# RF_Xbee.net
KiCad netlist of a schematic drawn in Altium Designer
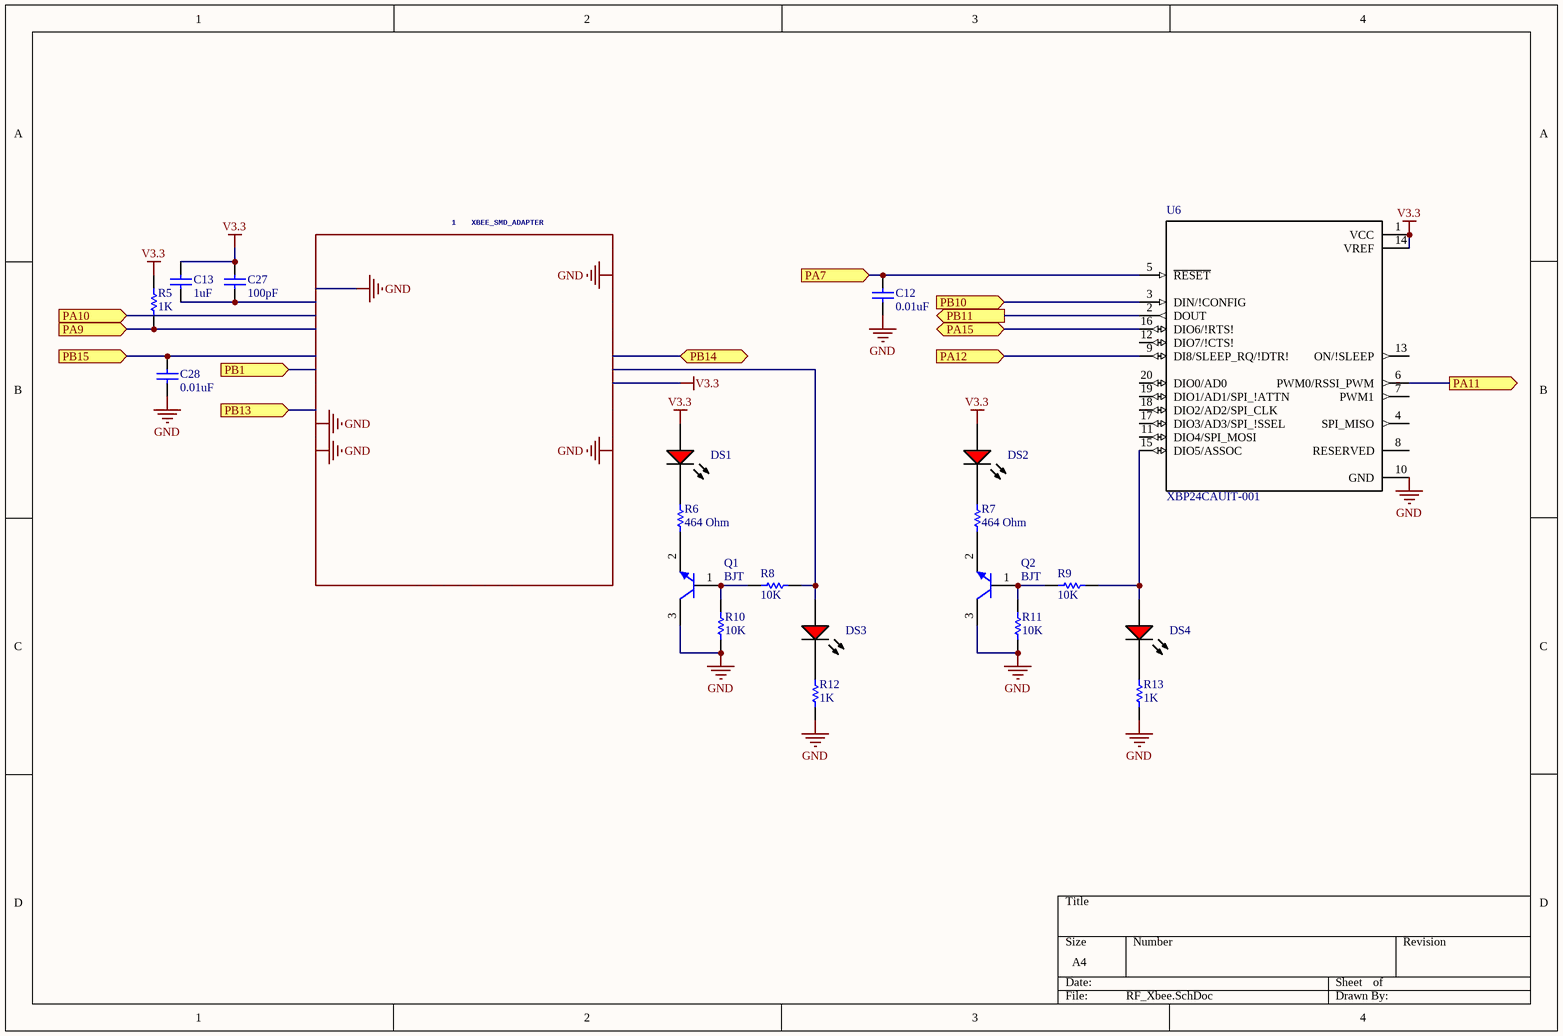
[diagram p0: RF_Xbee.SchDoc]

(export (version "E")
  (design (tool "Eeschema 10.0.6"))
  (components
    (comp (ref "1")
      (value "XBEE_SMD_ADAPTER")
      (footprint "XBEE_SMD_ADAPTER")
      (fields (field (name "LIBRARYNAME") "UBCSolar"))
      (libsource (lib "UBCSolar") (part "XBEE_SMD_ADAPTER"))
    )
    (comp (ref "C12")
      (value "0.01uF")
      (footprint "CAPC1206(3216)170_M")
      (description "CAP 10nF 50V ±5% 1206 (3216 Metric) Thickness 1.7mm SMD")
      (fields (field (name "TOLERANCE") "Â±5%"))
      (libsource (lib "Altium Content Vault") (part "CAP"))
    )
    (comp (ref "C13")
      (value "1uF")
      (footprint "CAPC3216X180X50ML20T25")
      (description "Chip Capacitor, 1 uF, +/- 10%, 25 V, -55 to 125 degC, 1206 (3216 Metric), RoHS, Tape and Reel")
      (fields (field (name "MANUFACTURER") "Kemet") (field (name "TOLERANCE") "10%"))
      (libsource (lib "Altium Content Vault") (part "CAP-NP-2"))
    )
    (comp (ref "C27")
      (value "100pF")
      (footprint "CAPC2013X88X50ML20T25")
      (fields (field (name "MANUFACTURER") "Kemet") (field (name "PART NUMBER") "C0805C101J2GACTU"))
      (libsource (lib "Altium Content Vault") (part "CAP"))
    )
    (comp (ref "C28")
      (value "0.01uF")
      (footprint "CAPC1206(3216)170_M")
      (description "CAP 10nF 50V ±5% 1206 (3216 Metric) Thickness 1.7mm SMD")
      (fields (field (name "TOLERANCE") "Â±5%"))
      (libsource (lib "Altium Content Vault") (part "CAP"))
    )
    (comp (ref "DS1")
      (value "HSMH-C150")
      (footprint "AVAG-HSMX-C150_V")
      (description "LED Uni-Color Red, 65 mW, 25 mA, -40 to 85 degC, 2-Pin SMD, RoHS, Tape and Reel")
      (fields (field (name "MANUFACTURER") "Avago"))
      (libsource (lib "Altium Content Vault") (part "LED-RED-AK-2"))
    )
    (comp (ref "DS2")
      (value "HSMH-C150")
      (footprint "AVAG-HSMX-C150_V")
      (description "LED Uni-Color Red, 65 mW, 25 mA, -40 to 85 degC, 2-Pin SMD, RoHS, Tape and Reel")
      (fields (field (name "MANUFACTURER") "Avago"))
      (libsource (lib "Altium Content Vault") (part "LED-RED-AK-2"))
    )
    (comp (ref "DS3")
      (value "HSMH-C150")
      (footprint "AVAG-HSMX-C150_V")
      (description "LED Uni-Color Red, 65 mW, 25 mA, -40 to 85 degC, 2-Pin SMD, RoHS, Tape and Reel")
      (fields (field (name "MANUFACTURER") "Avago"))
      (libsource (lib "Altium Content Vault") (part "LED-RED-AK-2"))
    )
    (comp (ref "DS4")
      (value "HSMH-C150")
      (footprint "AVAG-HSMX-C150_V")
      (description "LED Uni-Color Red, 65 mW, 25 mA, -40 to 85 degC, 2-Pin SMD, RoHS, Tape and Reel")
      (fields (field (name "MANUFACTURER") "Avago"))
      (libsource (lib "Altium Content Vault") (part "LED-RED-AK-2"))
    )
    (comp (ref "Q1")
      (value "BJT")
      (footprint "ONSC-SOT-23-3-318-08_V")
      (description "General Purpose Transistor, NPN Silicon, 3-Pin SOT-23, Pb-Free, Tape and Reel")
      (fields (field (name "MANUFACTURER") "On Semiconductor") (field (name "PARTNUMBER") "MMBT3904LT1G"))
      (libsource (lib "Altium Content Vault") (part "ONSC-NPN-B1E2C3-3"))
    )
    (comp (ref "Q2")
      (value "BJT")
      (footprint "ONSC-SOT-23-3-318-08_V")
      (description "General Purpose Transistor, NPN Silicon, 3-Pin SOT-23, Pb-Free, Tape and Reel")
      (fields (field (name "MANUFACTURER") "On Semiconductor") (field (name "PARTNUMBER") "MMBT3904LT1G"))
      (libsource (lib "Altium Content Vault") (part "ONSC-NPN-B1E2C3-3"))
    )
    (comp (ref "R5")
      (value "1K")
      (footprint "RESC2013X50X30NL20T20")
      (fields (field (name "PART NUMBER") "CRCW08051K00FKEA") (field (name "MANUFACTURER") "Vishay Dale"))
      (libsource (lib "Altium Content Vault") (part "RES"))
    )
    (comp (ref "R6")
      (value "464 Ohm")
      (footprint "RESC3216X70X50NL05T20")
      (fields (field (name "PART NUMBER") "ERJ-8ENF4640V") (field (name "MANUFACTURER") "Panasonic"))
      (libsource (lib "Altium Content Vault") (part "RES"))
    )
    (comp (ref "R7")
      (value "464 Ohm")
      (footprint "RESC3216X70X50NL05T20")
      (fields (field (name "PART NUMBER") "ERJ-8ENF4640V") (field (name "MANUFACTURER") "Panasonic"))
      (libsource (lib "Altium Content Vault") (part "RES"))
    )
    (comp (ref "R8")
      (value "10K")
      (footprint "RESC1609X50X30NL8T20")
      (description "Chip Resistor, 10 KOhm, +/- 1%, 100 mW, -55 to 155 degC, 0603 (1608 Metric), RoHS, Tape and Reel")
      (fields (field (name "MANUFACTURER") "Vishay Semiconductor"))
      (libsource (lib "Altium Content Vault") (part "RES-2"))
    )
    (comp (ref "R9")
      (value "10K")
      (footprint "RESC1609X50X30NL8T20")
      (description "Chip Resistor, 10 KOhm, +/- 1%, 100 mW, -55 to 155 degC, 0603 (1608 Metric), RoHS, Tape and Reel")
      (fields (field (name "MANUFACTURER") "Vishay Semiconductor"))
      (libsource (lib "Altium Content Vault") (part "RES-2"))
    )
    (comp (ref "R10")
      (value "10K")
      (footprint "RESC1609X50X30NL8T20")
      (description "Chip Resistor, 10 KOhm, +/- 1%, 100 mW, -55 to 155 degC, 0603 (1608 Metric), RoHS, Tape and Reel")
      (fields (field (name "MANUFACTURER") "Vishay Semiconductor"))
      (libsource (lib "Altium Content Vault") (part "RES-2"))
    )
    (comp (ref "R11")
      (value "10K")
      (footprint "RESC1609X50X30NL8T20")
      (description "Chip Resistor, 10 KOhm, +/- 1%, 100 mW, -55 to 155 degC, 0603 (1608 Metric), RoHS, Tape and Reel")
      (fields (field (name "MANUFACTURER") "Vishay Semiconductor"))
      (libsource (lib "Altium Content Vault") (part "RES-2"))
    )
    (comp (ref "R12")
      (value "1K")
      (footprint "RESC2013X50X30NL20T20")
      (fields (field (name "PART NUMBER") "CRCW08051K00FKEA") (field (name "MANUFACTURER") "Vishay Dale"))
      (libsource (lib "Altium Content Vault") (part "RES"))
    )
    (comp (ref "R13")
      (value "1K")
      (footprint "RESC2013X50X30NL20T20")
      (fields (field (name "PART NUMBER") "CRCW08051K00FKEA") (field (name "MANUFACTURER") "Vishay Dale"))
      (libsource (lib "Altium Content Vault") (part "RES"))
    )
    (comp (ref "U6")
      (value "XBP24CAUIT-001")
      (footprint "*MODULE_XBP24CAUIT-001")
      (description "802.15.4 Transceiver Module 2.4GHz Antenna Not Included, U.FL Through Hole")
      (fields (field (name "MF") "Digi International"))
      (libsource (lib "XBP24CAUIT-001") (part "XBP24CAUIT-001"))
    )
  )
  (nets
    (net (code "1") (name "/PA7") (class "Default")
      (node (ref "C12") (pin "2") (pinfunction "2_2") (pintype "passive"))
      (node (ref "U6") (pin "5") (pinfunction "~{RESET}_5") (pintype "input"))
    )
    (net (code "2") (name "/PA9") (class "Default")
      (node (ref "1") (pin "4") (pinfunction "P$4_4") (pintype "bidirectional"))
      (node (ref "R5") (pin "1") (pinfunction "1_1") (pintype "passive"))
    )
    (net (code "3") (name "/PA10") (class "Default")
      (node (ref "1") (pin "3") (pinfunction "P$3_3") (pintype "bidirectional"))
    )
    (net (code "4") (name "/PA11") (class "Default")
      (node (ref "U6") (pin "6") (pinfunction "PWM0/RSSI_PWM_6") (pintype "output"))
    )
    (net (code "5") (name "/PA12") (class "Default")
      (node (ref "U6") (pin "9") (pinfunction "DI8/SLEEP_RQ/!DTR!_9") (pintype "bidirectional"))
    )
    (net (code "6") (name "/PA15") (class "Default")
      (node (ref "U6") (pin "16") (pinfunction "DIO6/!RTS!_16") (pintype "bidirectional"))
    )
    (net (code "7") (name "/PB1") (class "Default")
      (node (ref "1") (pin "7") (pinfunction "P$7_7") (pintype "bidirectional"))
    )
    (net (code "8") (name "/PB10") (class "Default")
      (node (ref "U6") (pin "3") (pinfunction "DIN/!CONFIG_3") (pintype "input"))
    )
    (net (code "9") (name "/PB11") (class "Default")
      (node (ref "U6") (pin "2") (pinfunction "DOUT_2") (pintype "output"))
    )
    (net (code "10") (name "/PB13") (class "Default")
      (node (ref "1") (pin "10") (pinfunction "P$10_10") (pintype "bidirectional"))
    )
    (net (code "11") (name "/PB14") (class "Default")
      (node (ref "1") (pin "29") (pinfunction "P$29_29") (pintype "bidirectional"))
    )
    (net (code "12") (name "/PB15") (class "Default")
      (node (ref "1") (pin "6") (pinfunction "P$6_6") (pintype "bidirectional"))
      (node (ref "C28") (pin "2") (pinfunction "2_2") (pintype "passive"))
    )
    (net (code "13") (name "GND") (class "Default")
      (node (ref "1") (pin "1") (pinfunction "P$1_1") (pintype "bidirectional"))
      (node (ref "1") (pin "11") (pinfunction "P$11_11") (pintype "bidirectional"))
      (node (ref "1") (pin "13") (pinfunction "P$13_13") (pintype "bidirectional"))
      (node (ref "1") (pin "22") (pinfunction "P$22_22") (pintype "bidirectional"))
      (node (ref "1") (pin "35") (pinfunction "P$35_35") (pintype "bidirectional"))
      (node (ref "C12") (pin "1") (pinfunction "1_1") (pintype "passive"))
      (node (ref "C28") (pin "1") (pinfunction "1_1") (pintype "passive"))
      (node (ref "Q1") (pin "3") (pinfunction "C_3") (pintype "passive"))
      (node (ref "Q2") (pin "3") (pinfunction "C_3") (pintype "passive"))
      (node (ref "R10") (pin "2") (pinfunction "2_2") (pintype "passive"))
      (node (ref "R11") (pin "2") (pinfunction "2_2") (pintype "passive"))
      (node (ref "R12") (pin "1") (pinfunction "1_1") (pintype "passive"))
      (node (ref "R13") (pin "1") (pinfunction "1_1") (pintype "passive"))
      (node (ref "U6") (pin "10") (pinfunction "GND_10") (pintype "power_in"))
    )
    (net (code "14") (name "Net-(1-P$2)") (class "Default")
      (node (ref "1") (pin "2") (pinfunction "P$2_2") (pintype "bidirectional"))
      (node (ref "C13") (pin "1") (pinfunction "1_1") (pintype "passive"))
      (node (ref "C27") (pin "1") (pinfunction "1_1") (pintype "passive"))
    )
    (net (code "15") (name "Net-(1-P$28)") (class "Default")
      (node (ref "1") (pin "28") (pinfunction "P$28_28") (pintype "bidirectional"))
      (node (ref "DS3") (pin "1") (pinfunction "A_1") (pintype "passive"))
      (node (ref "R8") (pin "1") (pinfunction "1_1") (pintype "passive"))
    )
    (net (code "16") (name "Net-(DS1-K)") (class "Default")
      (node (ref "DS1") (pin "2") (pinfunction "K_2") (pintype "passive"))
      (node (ref "R6") (pin "2") (pinfunction "2_2") (pintype "passive"))
    )
    (net (code "17") (name "Net-(DS2-K)") (class "Default")
      (node (ref "DS2") (pin "2") (pinfunction "K_2") (pintype "passive"))
      (node (ref "R7") (pin "2") (pinfunction "2_2") (pintype "passive"))
    )
    (net (code "18") (name "Net-(DS3-K)") (class "Default")
      (node (ref "DS3") (pin "2") (pinfunction "K_2") (pintype "passive"))
      (node (ref "R12") (pin "2") (pinfunction "2_2") (pintype "passive"))
    )
    (net (code "19") (name "Net-(DS4-A)") (class "Default")
      (node (ref "DS4") (pin "1") (pinfunction "A_1") (pintype "passive"))
      (node (ref "R9") (pin "1") (pinfunction "1_1") (pintype "passive"))
      (node (ref "U6") (pin "15") (pinfunction "DIO5/ASSOC_15") (pintype "bidirectional"))
    )
    (net (code "20") (name "Net-(DS4-K)") (class "Default")
      (node (ref "DS4") (pin "2") (pinfunction "K_2") (pintype "passive"))
      (node (ref "R13") (pin "2") (pinfunction "2_2") (pintype "passive"))
    )
    (net (code "21") (name "Net-(Q1-B)") (class "Default")
      (node (ref "Q1") (pin "1") (pinfunction "B_1") (pintype "passive"))
      (node (ref "R10") (pin "1") (pinfunction "1_1") (pintype "passive"))
      (node (ref "R8") (pin "2") (pinfunction "2_2") (pintype "passive"))
    )
    (net (code "22") (name "Net-(Q1-E)") (class "Default")
      (node (ref "Q1") (pin "2") (pinfunction "E_2") (pintype "passive"))
      (node (ref "R6") (pin "1") (pinfunction "1_1") (pintype "passive"))
    )
    (net (code "23") (name "Net-(Q2-B)") (class "Default")
      (node (ref "Q2") (pin "1") (pinfunction "B_1") (pintype "passive"))
      (node (ref "R11") (pin "1") (pinfunction "1_1") (pintype "passive"))
      (node (ref "R9") (pin "2") (pinfunction "2_2") (pintype "passive"))
    )
    (net (code "24") (name "Net-(Q2-E)") (class "Default")
      (node (ref "Q2") (pin "2") (pinfunction "E_2") (pintype "passive"))
      (node (ref "R7") (pin "1") (pinfunction "1_1") (pintype "passive"))
    )
    (net (code "25") (name "V3.3") (class "Default")
      (node (ref "1") (pin "27") (pinfunction "P$27_27") (pintype "bidirectional"))
      (node (ref "C13") (pin "2") (pinfunction "2_2") (pintype "passive"))
      (node (ref "C27") (pin "2") (pinfunction "2_2") (pintype "passive"))
      (node (ref "DS1") (pin "1") (pinfunction "A_1") (pintype "passive"))
      (node (ref "DS2") (pin "1") (pinfunction "A_1") (pintype "passive"))
      (node (ref "R5") (pin "2") (pinfunction "2_2") (pintype "passive"))
      (node (ref "U6") (pin "1") (pinfunction "VCC_1") (pintype "power_in"))
      (node (ref "U6") (pin "14") (pinfunction "VREF_14") (pintype "power_in"))
    )
    (net (code "26") (name "unconnected-(1-P$5-Pad5)") (class "Default")
      (node (ref "1") (pin "5") (pinfunction "P$5_5") (pintype "bidirectional"))
    )
    (net (code "27") (name "unconnected-(1-P$8-Pad8)") (class "Default")
      (node (ref "1") (pin "8") (pinfunction "P$8_8") (pintype "bidirectional"))
    )
    (net (code "28") (name "unconnected-(1-P$9-Pad9)") (class "Default")
      (node (ref "1") (pin "9") (pinfunction "P$9_9") (pintype "bidirectional"))
    )
    (net (code "29") (name "unconnected-(1-P$12-Pad12)") (class "Default")
      (node (ref "1") (pin "12") (pinfunction "P$12_12") (pintype "bidirectional"))
    )
    (net (code "30") (name "unconnected-(1-P$14-Pad14)") (class "Default")
      (node (ref "1") (pin "14") (pinfunction "P$14_14") (pintype "bidirectional"))
    )
    (net (code "31") (name "unconnected-(1-P$15-Pad15)") (class "Default")
      (node (ref "1") (pin "15") (pinfunction "P$15_15") (pintype "bidirectional"))
    )
    (net (code "32") (name "unconnected-(1-P$16-Pad16)") (class "Default")
      (node (ref "1") (pin "16") (pinfunction "P$16_16") (pintype "bidirectional"))
    )
    (net (code "33") (name "unconnected-(1-P$17-Pad17)") (class "Default")
      (node (ref "1") (pin "17") (pinfunction "P$17_17") (pintype "bidirectional"))
    )
    (net (code "34") (name "unconnected-(1-P$18-Pad18)") (class "Default")
      (node (ref "1") (pin "18") (pinfunction "P$18_18") (pintype "bidirectional"))
    )
    (net (code "35") (name "unconnected-(1-P$19-Pad19)") (class "Default")
      (node (ref "1") (pin "19") (pinfunction "P$19_19") (pintype "bidirectional"))
    )
    (net (code "36") (name "unconnected-(1-P$20-Pad20)") (class "Default")
      (node (ref "1") (pin "20") (pinfunction "P$20_20") (pintype "bidirectional"))
    )
    (net (code "37") (name "unconnected-(1-P$21-Pad21)") (class "Default")
      (node (ref "1") (pin "21") (pinfunction "P$21_21") (pintype "bidirectional"))
    )
    (net (code "38") (name "unconnected-(1-P$23-Pad23)") (class "Default")
      (node (ref "1") (pin "23") (pinfunction "P$23_23") (pintype "bidirectional"))
    )
    (net (code "39") (name "unconnected-(1-P$24-Pad24)") (class "Default")
      (node (ref "1") (pin "24") (pinfunction "P$24_24") (pintype "bidirectional"))
    )
    (net (code "40") (name "unconnected-(1-P$25-Pad25)") (class "Default")
      (node (ref "1") (pin "25") (pinfunction "P$25_25") (pintype "bidirectional"))
    )
    (net (code "41") (name "unconnected-(1-P$26-Pad26)") (class "Default")
      (node (ref "1") (pin "26") (pinfunction "P$26_26") (pintype "bidirectional"))
    )
    (net (code "42") (name "unconnected-(1-P$30-Pad30)") (class "Default")
      (node (ref "1") (pin "30") (pinfunction "P$30_30") (pintype "bidirectional"))
    )
    (net (code "43") (name "unconnected-(1-P$31-Pad31)") (class "Default")
      (node (ref "1") (pin "31") (pinfunction "P$31_31") (pintype "bidirectional"))
    )
    (net (code "44") (name "unconnected-(1-P$32-Pad32)") (class "Default")
      (node (ref "1") (pin "32") (pinfunction "P$32_32") (pintype "bidirectional"))
    )
    (net (code "45") (name "unconnected-(1-P$33-Pad33)") (class "Default")
      (node (ref "1") (pin "33") (pinfunction "P$33_33") (pintype "bidirectional"))
    )
    (net (code "46") (name "unconnected-(1-P$34-Pad34)") (class "Default")
      (node (ref "1") (pin "34") (pinfunction "P$34_34") (pintype "bidirectional"))
    )
    (net (code "47") (name "unconnected-(1-P$36-Pad36)") (class "Default")
      (node (ref "1") (pin "36") (pinfunction "P$36_36") (pintype "bidirectional"))
    )
    (net (code "48") (name "unconnected-(1-P$37-Pad37)") (class "Default")
      (node (ref "1") (pin "37") (pinfunction "P$37_37") (pintype "bidirectional"))
    )
    (net (code "49") (name "unconnected-(U6-DIO0{slash}AD0-Pad20)") (class "Default")
      (node (ref "U6") (pin "20") (pinfunction "DIO0/AD0_20") (pintype "bidirectional"))
    )
    (net (code "50") (name "unconnected-(U6-DIO1{slash}AD1{slash}SPI_!ATTN-Pad19)") (class "Default")
      (node (ref "U6") (pin "19") (pinfunction "DIO1/AD1/SPI_!ATTN_19") (pintype "bidirectional"))
    )
    (net (code "51") (name "unconnected-(U6-DIO2{slash}AD2{slash}SPI_CLK-Pad18)") (class "Default")
      (node (ref "U6") (pin "18") (pinfunction "DIO2/AD2/SPI_CLK_18") (pintype "bidirectional"))
    )
    (net (code "52") (name "unconnected-(U6-DIO3{slash}AD3{slash}SPI_!SSEL-Pad17)") (class "Default")
      (node (ref "U6") (pin "17") (pinfunction "DIO3/AD3/SPI_!SSEL_17") (pintype "bidirectional"))
    )
    (net (code "53") (name "unconnected-(U6-DIO4{slash}SPI_MOSI-Pad11)") (class "Default")
      (node (ref "U6") (pin "11") (pinfunction "DIO4/SPI_MOSI_11") (pintype "bidirectional"))
    )
    (net (code "54") (name "unconnected-(U6-DIO7{slash}!CTS!-Pad12)") (class "Default")
      (node (ref "U6") (pin "12") (pinfunction "DIO7/!CTS!_12") (pintype "bidirectional"))
    )
    (net (code "55") (name "unconnected-(U6-ON{slash}!SLEEP-Pad13)") (class "Default")
      (node (ref "U6") (pin "13") (pinfunction "ON/!SLEEP_13") (pintype "output"))
    )
    (net (code "56") (name "unconnected-(U6-PWM1-Pad7)") (class "Default")
      (node (ref "U6") (pin "7") (pinfunction "PWM1_7") (pintype "output"))
    )
    (net (code "57") (name "unconnected-(U6-RESERVED-Pad8)") (class "Default")
      (node (ref "U6") (pin "8") (pinfunction "RESERVED_8") (pintype "passive"))
    )
    (net (code "58") (name "unconnected-(U6-SPI_MISO-Pad4)") (class "Default")
      (node (ref "U6") (pin "4") (pinfunction "SPI_MISO_4") (pintype "output"))
    )
  )
)
